# LunettaAV_WIP.net
KiCad netlist of a schematic drawn in EAGLE
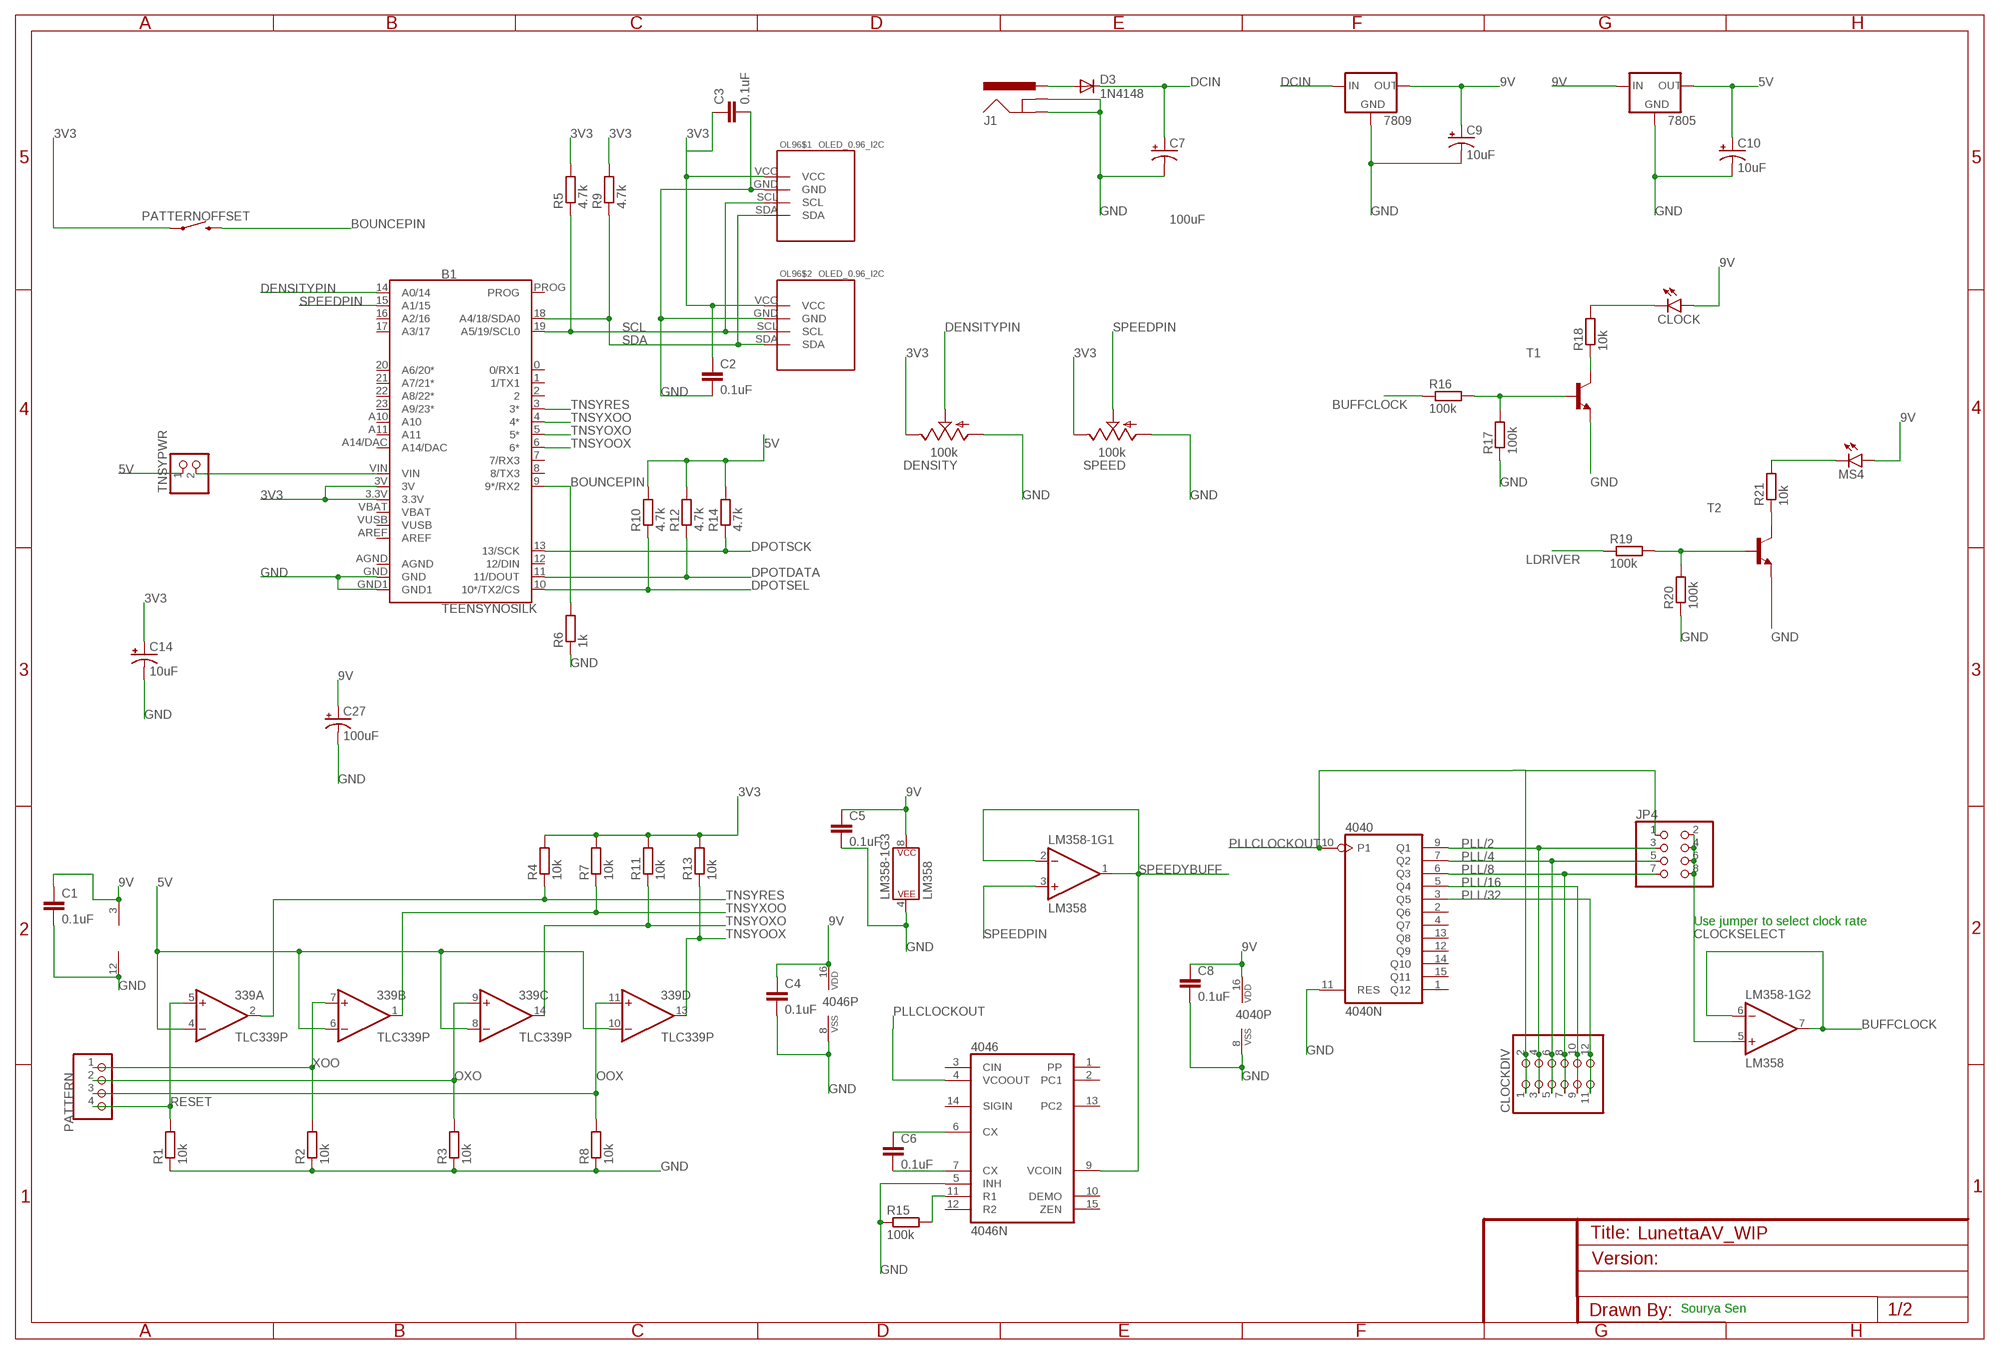
[diagram p0: schematic, sheet 1]
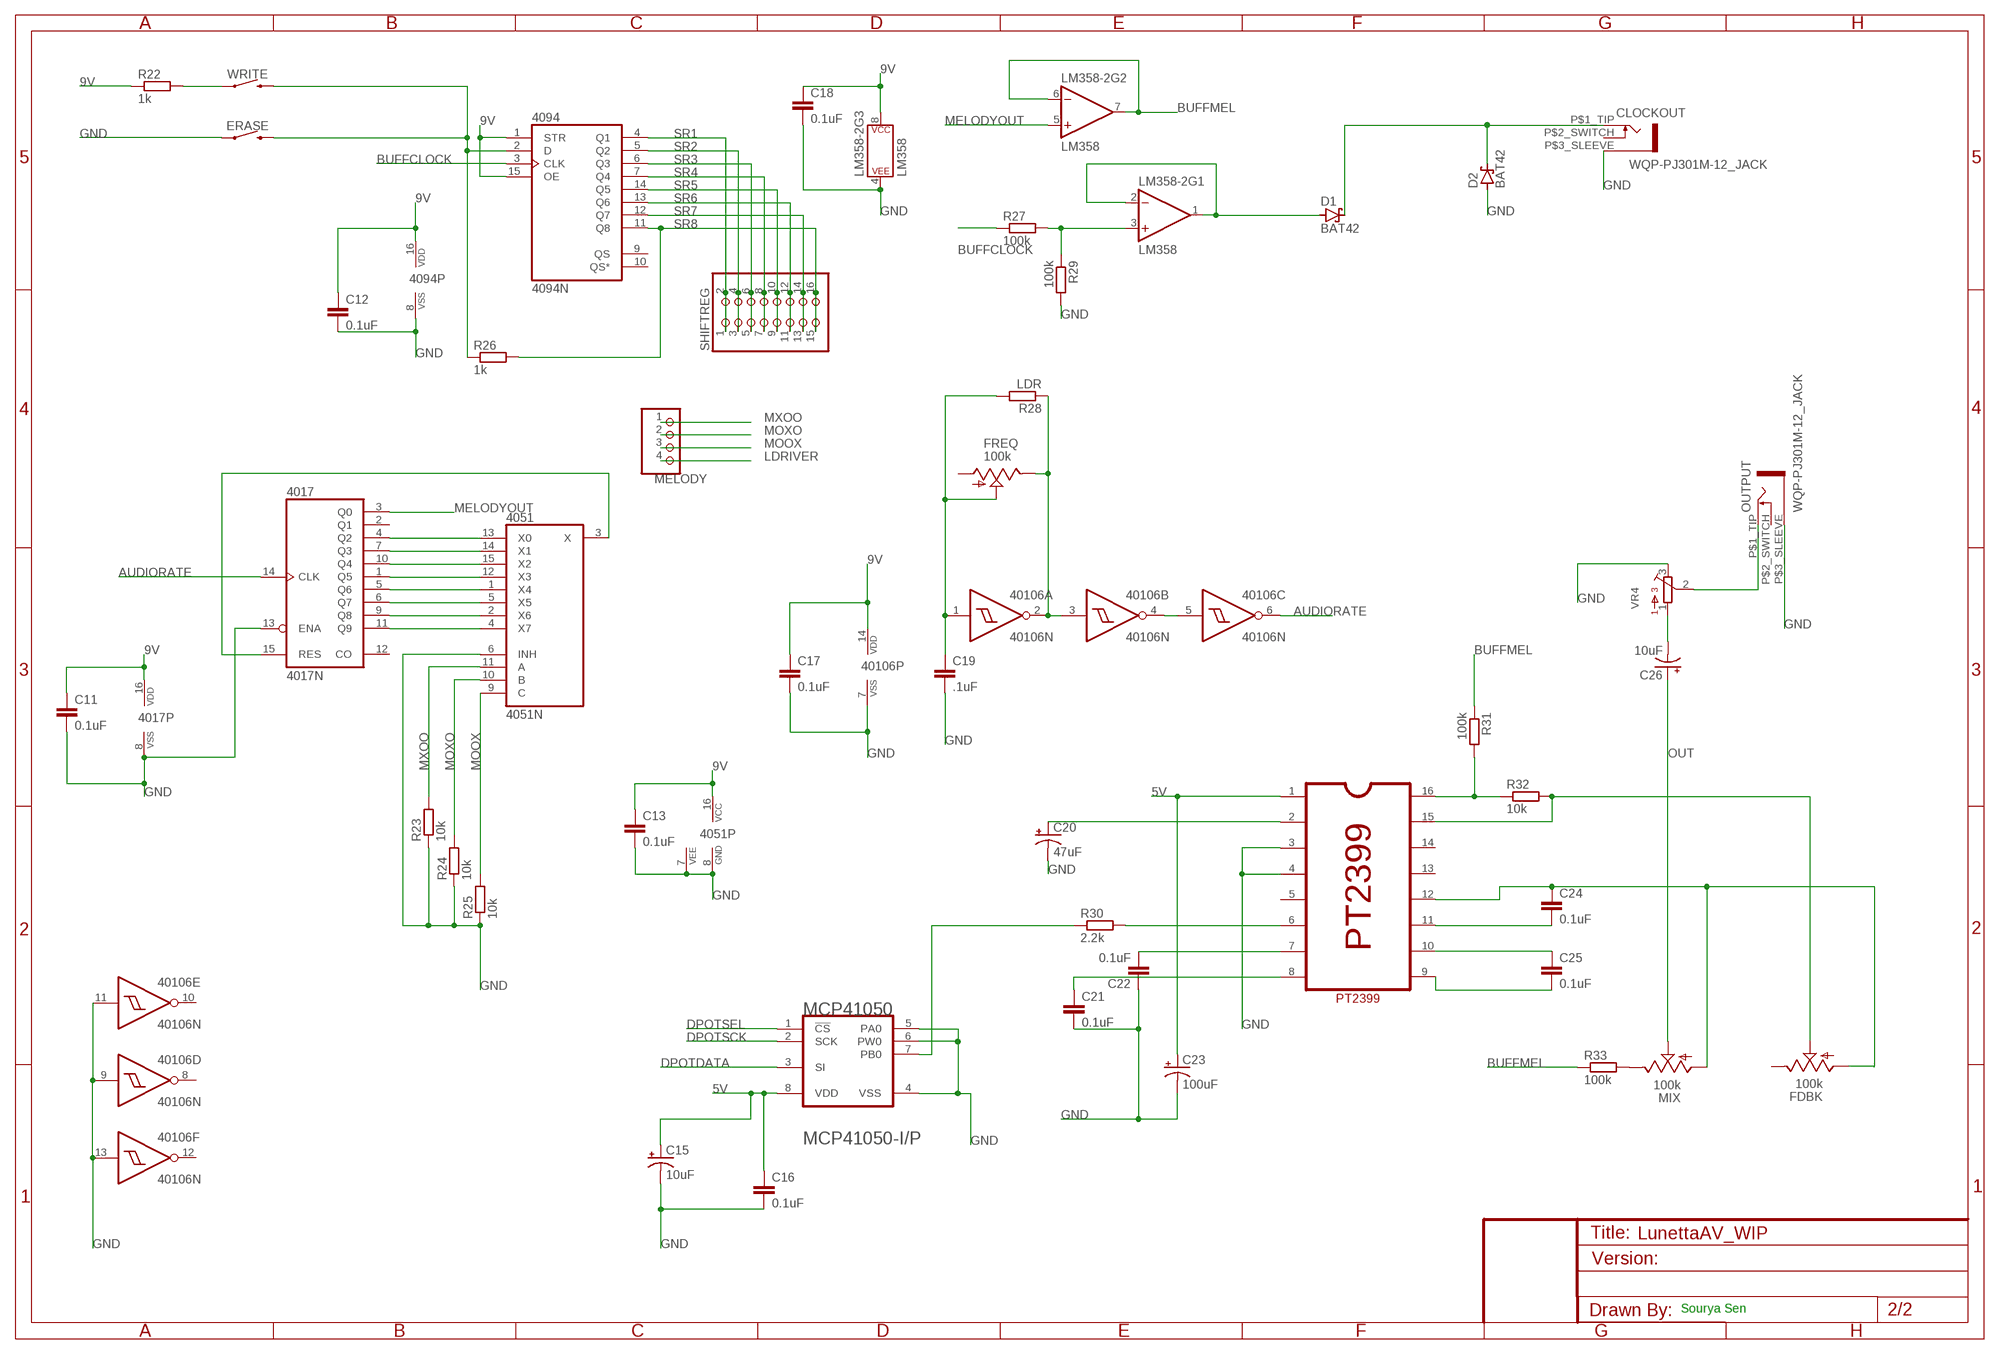
[diagram p1: schematic, sheet 2]

(export (version "E")
  (design (tool "Eeschema 10.0.6"))
  (components
    (comp (ref "4017")
      (value "4017N")
      (footprint "eagle-import:DIL16")
      (libsource (lib "eagle-import") (part "4017N"))
    )
    (comp (ref "4051")
      (value "4051N")
      (footprint "eagle-import:DIL16")
      (libsource (lib "eagle-import") (part "4051N"))
    )
    (comp (ref "4094")
      (value "4094N")
      (footprint "eagle-import:DIL16")
      (libsource (lib "eagle-import") (part "4094N"))
    )
    (comp (ref "40106")
      (value "40106N")
      (footprint "eagle-import:DIL14")
      (libsource (lib "eagle-import") (part "40106N"))
    )
    (comp (ref "C11")
      (value "0.1uF")
      (footprint "eagle-import:CAP-PTH-SMALL-KIT")
      (libsource (lib "eagle-import") (part "0.1UF-KIT-EZ-50V-20%"))
    )
    (comp (ref "C12")
      (value "0.1uF")
      (footprint "eagle-import:CAP-PTH-SMALL-KIT")
      (libsource (lib "eagle-import") (part "0.1UF-KIT-EZ-50V-20%"))
    )
    (comp (ref "C13")
      (value "0.1uF")
      (footprint "eagle-import:CAP-PTH-SMALL-KIT")
      (libsource (lib "eagle-import") (part "0.1UF-KIT-EZ-50V-20%"))
    )
    (comp (ref "C15")
      (value "10uF")
      (footprint "eagle-import:CPOL-RADIAL-2.5MM-5MM")
      (libsource (lib "eagle-import") (part "10UF-POLAR-RADIAL-2.5MM-25V-20%"))
    )
    (comp (ref "C16")
      (value "0.1uF")
      (footprint "eagle-import:CAP-PTH-SMALL-KIT")
      (libsource (lib "eagle-import") (part "0.1UF-KIT-EZ-50V-20%"))
    )
    (comp (ref "C17")
      (value "0.1uF")
      (footprint "eagle-import:CAP-PTH-SMALL-KIT")
      (libsource (lib "eagle-import") (part "0.1UF-KIT-EZ-50V-20%"))
    )
    (comp (ref "C18")
      (value "0.1uF")
      (footprint "eagle-import:CAP-PTH-SMALL-KIT")
      (libsource (lib "eagle-import") (part "0.1UF-KIT-EZ-50V-20%"))
    )
    (comp (ref "C19")
      (value ".1uF")
      (footprint "eagle-import:C5B3.5")
      (libsource (lib "eagle-import") (part "C5/3.5"))
    )
    (comp (ref "C20")
      (value "47uF")
      (footprint "eagle-import:CPOL-RADIAL-2.5MM-5MM")
      (libsource (lib "eagle-import") (part "10UF-POLAR-RADIAL-2.5MM-25V-20%"))
    )
    (comp (ref "C21")
      (value "0.1uF")
      (footprint "eagle-import:CAP-PTH-SMALL-KIT")
      (libsource (lib "eagle-import") (part "0.1UF-KIT-EZ-50V-20%"))
    )
    (comp (ref "C22")
      (value "0.1uF")
      (footprint "eagle-import:CAP-PTH-SMALL-KIT")
      (libsource (lib "eagle-import") (part "0.1UF-KIT-EZ-50V-20%"))
    )
    (comp (ref "C23")
      (value "100uF")
      (footprint "eagle-import:CPOL-RADIAL-2.5MM-6.5MM")
      (libsource (lib "eagle-import") (part "100UF-POLAR-RADIAL-2.5MM-25V-20%"))
    )
    (comp (ref "C24")
      (value "0.1uF")
      (footprint "eagle-import:CAP-PTH-SMALL-KIT")
      (libsource (lib "eagle-import") (part "0.1UF-KIT-EZ-50V-20%"))
    )
    (comp (ref "C25")
      (value "0.1uF")
      (footprint "eagle-import:CAP-PTH-SMALL-KIT")
      (libsource (lib "eagle-import") (part "0.1UF-KIT-EZ-50V-20%"))
    )
    (comp (ref "C26")
      (value "10uF")
      (footprint "eagle-import:CPOL-RADIAL-2.5MM-5MM")
      (libsource (lib "eagle-import") (part "10UF-POLAR-RADIAL-2.5MM-25V-20%"))
    )
    (comp (ref "CLOCKOUT")
      (value "WQP-PJ301M-12_JACK")
      (footprint "eagle-import:WQP-PJ301M-12_JACK")
      (libsource (lib "eagle-import") (part "WQP-PJ301M-12_JACK"))
    )
    (comp (ref "D1")
      (value "BAT42")
      (footprint "eagle-import:DO35-10")
      (libsource (lib "eagle-import") (part "BAT42"))
    )
    (comp (ref "D2")
      (value "BAT42")
      (footprint "eagle-import:DO35-10")
      (libsource (lib "eagle-import") (part "BAT42"))
    )
    (comp (ref "ERASE")
      (value "MOMENTARY-SWITCH-SPST-PTH-12MM")
      (footprint "eagle-import:TACTILE_SWITCH_PTH_12MM")
      (libsource (lib "eagle-import") (part "MOMENTARY-SWITCH-SPST-PTH-12MM"))
    )
    (comp (ref "FDBK")
      (value "100k")
      (footprint "eagle-import:9MM_SNAP-IN_POT")
      (libsource (lib "eagle-import") (part "9MM_SNAP-IN_POT_"))
    )
    (comp (ref "FREQ")
      (value "100k")
      (footprint "eagle-import:9MM_SNAP-IN_POT")
      (libsource (lib "eagle-import") (part "9MM_SNAP-IN_POT_"))
    )
    (comp (ref "LM358-2")
      (value "LM358")
      (footprint "eagle-import:DIP08")
      (libsource (lib "eagle-import") (part "LM358"))
    )
    (comp (ref "MCP41050")
      (value "MCP41050")
      (footprint "eagle-import:MICROCHIP_MCP41050-I-P_0")
      (fields (field (name "MF") "Microchip") (field (name "MPN") "MCP41050-I/P"))
      (libsource (lib "eagle-import") (part "MICROCHIP_MCP41050-I-PMICROCHIP_MCP41050-I-P_0_0"))
    )
    (comp (ref "MELODY")
      (value "PINHD-1X4")
      (footprint "eagle-import:1X04")
      (libsource (lib "eagle-import") (part "PINHD-1X4"))
    )
    (comp (ref "MIX")
      (value "100k")
      (footprint "eagle-import:9MM_SNAP-IN_POT")
      (libsource (lib "eagle-import") (part "9MM_SNAP-IN_POT_"))
    )
    (comp (ref "OUTPUT")
      (value "WQP-PJ301M-12_JACK")
      (footprint "eagle-import:WQP-PJ301M-12_JACK")
      (libsource (lib "eagle-import") (part "WQP-PJ301M-12_JACK"))
    )
    (comp (ref "PT2399")
      (value "PT2399")
      (footprint "eagle-import:DIP-16")
      (libsource (lib "eagle-import") (part "PT2399"))
    )
    (comp (ref "R22")
      (value "1k")
      (footprint "eagle-import:7MM_RESISTOR")
      (libsource (lib "eagle-import") (part "RESISTOR7MM"))
    )
    (comp (ref "R23")
      (value "10k")
      (footprint "eagle-import:7MM_RESISTOR")
      (libsource (lib "eagle-import") (part "RESISTOR7MM"))
    )
    (comp (ref "R24")
      (value "10k")
      (footprint "eagle-import:7MM_RESISTOR")
      (libsource (lib "eagle-import") (part "RESISTOR7MM"))
    )
    (comp (ref "R25")
      (value "10k")
      (footprint "eagle-import:7MM_RESISTOR")
      (libsource (lib "eagle-import") (part "RESISTOR7MM"))
    )
    (comp (ref "R26")
      (value "1k")
      (footprint "eagle-import:7MM_RESISTOR")
      (libsource (lib "eagle-import") (part "RESISTOR7MM"))
    )
    (comp (ref "R27")
      (value "100k")
      (footprint "eagle-import:7MM_RESISTOR")
      (libsource (lib "eagle-import") (part "RESISTOR7MM"))
    )
    (comp (ref "R28")
      (value "LDR")
      (footprint "eagle-import:0204V")
      (libsource (lib "eagle-import") (part "R-EU_0204/2V"))
    )
    (comp (ref "R29")
      (value "100k")
      (footprint "eagle-import:7MM_RESISTOR")
      (libsource (lib "eagle-import") (part "RESISTOR7MM"))
    )
    (comp (ref "R30")
      (value "2.2k")
      (footprint "eagle-import:7MM_RESISTOR")
      (libsource (lib "eagle-import") (part "RESISTOR7MM"))
    )
    (comp (ref "R31")
      (value "100k")
      (footprint "eagle-import:7MM_RESISTOR")
      (libsource (lib "eagle-import") (part "RESISTOR7MM"))
    )
    (comp (ref "R32")
      (value "10k")
      (footprint "eagle-import:7MM_RESISTOR")
      (libsource (lib "eagle-import") (part "RESISTOR7MM"))
    )
    (comp (ref "R33")
      (value "100k")
      (footprint "eagle-import:7MM_RESISTOR")
      (libsource (lib "eagle-import") (part "RESISTOR7MM"))
    )
    (comp (ref "SHIFTREG")
      (value "PINHD-2X8")
      (footprint "eagle-import:2X08")
      (libsource (lib "eagle-import") (part "PINHD-2X8"))
    )
    (comp (ref "VR4")
      (value "BOURNS_3362P_TRIMMERP")
      (footprint "eagle-import:BOURNS_3362P_TRIMMER")
      (libsource (lib "eagle-import") (part "BOURNS_3362P_TRIMMERP"))
    )
    (comp (ref "WRITE")
      (value "MOMENTARY-SWITCH-SPST-PTH-12MM")
      (footprint "eagle-import:TACTILE_SWITCH_PTH_12MM")
      (libsource (lib "eagle-import") (part "MOMENTARY-SWITCH-SPST-PTH-12MM"))
    )
    (comp (ref "339")
      (value "TLC339P")
      (footprint "eagle-import:DIL14")
      (libsource (lib "eagle-import") (part "TLC339P"))
    )
    (comp (ref "4040")
      (value "4040N")
      (footprint "eagle-import:DIL16")
      (libsource (lib "eagle-import") (part "4040N"))
    )
    (comp (ref "4046")
      (value "4046N")
      (footprint "eagle-import:DIL16")
      (libsource (lib "eagle-import") (part "4046N"))
    )
    (comp (ref "7805")
      (value "7805")
      (footprint "eagle-import:78XXS")
      (libsource (lib "eagle-import") (part "78XXS"))
    )
    (comp (ref "7809")
      (value "7809")
      (footprint "eagle-import:78XXS")
      (libsource (lib "eagle-import") (part "78XXS"))
    )
    (comp (ref "B1")
      (value "TEENSYNOSILK")
      (footprint "eagle-import:TEENSY_NOSILK")
      (libsource (lib "eagle-import") (part "TEENSYNOSILK"))
    )
    (comp (ref "C1")
      (value "0.1uF")
      (footprint "eagle-import:CAP-PTH-SMALL-KIT")
      (libsource (lib "eagle-import") (part "0.1UF-KIT-EZ-50V-20%"))
    )
    (comp (ref "C2")
      (value "0.1uF")
      (footprint "eagle-import:CAP-PTH-SMALL-KIT")
      (libsource (lib "eagle-import") (part "0.1UF-KIT-EZ-50V-20%"))
    )
    (comp (ref "C3")
      (value "0.1uF")
      (footprint "eagle-import:CAP-PTH-SMALL-KIT")
      (libsource (lib "eagle-import") (part "0.1UF-KIT-EZ-50V-20%"))
    )
    (comp (ref "C4")
      (value "0.1uF")
      (footprint "eagle-import:CAP-PTH-SMALL-KIT")
      (libsource (lib "eagle-import") (part "0.1UF-KIT-EZ-50V-20%"))
    )
    (comp (ref "C5")
      (value "0.1uF")
      (footprint "eagle-import:CAP-PTH-SMALL-KIT")
      (libsource (lib "eagle-import") (part "0.1UF-KIT-EZ-50V-20%"))
    )
    (comp (ref "C6")
      (value "0.1uF")
      (footprint "eagle-import:CAP-PTH-SMALL-KIT")
      (libsource (lib "eagle-import") (part "0.1UF-KIT-EZ-50V-20%"))
    )
    (comp (ref "C7")
      (value "100uF")
      (footprint "eagle-import:CPOL-RADIAL-2.5MM-6.5MM")
      (libsource (lib "eagle-import") (part "100UF-POLAR-RADIAL-2.5MM-25V-20%"))
    )
    (comp (ref "C8")
      (value "0.1uF")
      (footprint "eagle-import:CAP-PTH-SMALL-KIT")
      (libsource (lib "eagle-import") (part "0.1UF-KIT-EZ-50V-20%"))
    )
    (comp (ref "C9")
      (value "10uF")
      (footprint "eagle-import:CPOL-RADIAL-2.5MM-5MM")
      (libsource (lib "eagle-import") (part "10UF-POLAR-RADIAL-2.5MM-25V-20%"))
    )
    (comp (ref "C10")
      (value "10uF")
      (footprint "eagle-import:CPOL-RADIAL-2.5MM-5MM")
      (libsource (lib "eagle-import") (part "10UF-POLAR-RADIAL-2.5MM-25V-20%"))
    )
    (comp (ref "C14")
      (value "10uF")
      (footprint "eagle-import:CPOL-RADIAL-2.5MM-5MM")
      (libsource (lib "eagle-import") (part "10UF-POLAR-RADIAL-2.5MM-25V-20%"))
    )
    (comp (ref "C27")
      (value "100uF")
      (footprint "eagle-import:CPOL-RADIAL-2.5MM-6.5MM")
      (libsource (lib "eagle-import") (part "100UF-POLAR-RADIAL-2.5MM-25V-20%"))
    )
    (comp (ref "CLOCK")
      (value "LED3MM")
      (footprint "eagle-import:LED_3MM")
      (libsource (lib "eagle-import") (part "LED3MM"))
    )
    (comp (ref "CLOCKDIV")
      (value "PINHD-2X6")
      (footprint "eagle-import:2X06")
      (libsource (lib "eagle-import") (part "PINHD-2X6"))
    )
    (comp (ref "D3")
      (value "1N4148")
      (footprint "eagle-import:DO35-7")
      (libsource (lib "eagle-import") (part "SMALL_DIODEDO35-7"))
    )
    (comp (ref "DENSITY")
      (value "100k")
      (footprint "eagle-import:9MM_SNAP-IN_POT")
      (libsource (lib "eagle-import") (part "9MM_SNAP-IN_POT_"))
    )
    (comp (ref "J1")
      (value "POWER_JACKPOWER_JACK_SLOT")
      (footprint "eagle-import:POWER_JACK_PTH_SLOT")
      (libsource (lib "eagle-import") (part "POWER_JACKPOWER_JACK_SLOT"))
    )
    (comp (ref "JP4")
      (value "PINHD-2X4")
      (footprint "eagle-import:2X04")
      (libsource (lib "eagle-import") (part "PINHD-2X4"))
    )
    (comp (ref "LM358-1")
      (value "LM358")
      (footprint "eagle-import:DIP08")
      (libsource (lib "eagle-import") (part "LM358"))
    )
    (comp (ref "MS4")
      (value "LED3MM")
      (footprint "eagle-import:LED_3MM")
      (libsource (lib "eagle-import") (part "LED3MM"))
    )
    (comp (ref "OL96$1")
      (value "OLED_0.96_I2C")
      (footprint "eagle-import:OLED_0.96_I2C")
      (libsource (lib "eagle-import") (part "OLED_0.96_I2C"))
    )
    (comp (ref "OL96$2")
      (value "OLED_0.96_I2C")
      (footprint "eagle-import:OLED_0.96_I2C")
      (libsource (lib "eagle-import") (part "OLED_0.96_I2C"))
    )
    (comp (ref "PATTERN")
      (value "PINHD-1X4")
      (footprint "eagle-import:1X04")
      (libsource (lib "eagle-import") (part "PINHD-1X4"))
    )
    (comp (ref "PATTERNOFFSET")
      (value "MOMENTARY-SWITCH-SPST-PTH-12MM")
      (footprint "eagle-import:TACTILE_SWITCH_PTH_12MM")
      (libsource (lib "eagle-import") (part "MOMENTARY-SWITCH-SPST-PTH-12MM"))
    )
    (comp (ref "R1")
      (value "10k")
      (footprint "eagle-import:7MM_RESISTOR")
      (libsource (lib "eagle-import") (part "RESISTOR7MM"))
    )
    (comp (ref "R2")
      (value "10k")
      (footprint "eagle-import:7MM_RESISTOR")
      (libsource (lib "eagle-import") (part "RESISTOR7MM"))
    )
    (comp (ref "R3")
      (value "10k")
      (footprint "eagle-import:7MM_RESISTOR")
      (libsource (lib "eagle-import") (part "RESISTOR7MM"))
    )
    (comp (ref "R4")
      (value "10k")
      (footprint "eagle-import:7MM_RESISTOR")
      (libsource (lib "eagle-import") (part "RESISTOR7MM"))
    )
    (comp (ref "R5")
      (value "4.7k")
      (footprint "eagle-import:7MM_RESISTOR")
      (libsource (lib "eagle-import") (part "RESISTOR7MM"))
    )
    (comp (ref "R6")
      (value "1k")
      (footprint "eagle-import:7MM_RESISTOR")
      (libsource (lib "eagle-import") (part "RESISTOR7MM"))
    )
    (comp (ref "R7")
      (value "10k")
      (footprint "eagle-import:7MM_RESISTOR")
      (libsource (lib "eagle-import") (part "RESISTOR7MM"))
    )
    (comp (ref "R8")
      (value "10k")
      (footprint "eagle-import:7MM_RESISTOR")
      (libsource (lib "eagle-import") (part "RESISTOR7MM"))
    )
    (comp (ref "R9")
      (value "4.7k")
      (footprint "eagle-import:7MM_RESISTOR")
      (libsource (lib "eagle-import") (part "RESISTOR7MM"))
    )
    (comp (ref "R10")
      (value "4.7k")
      (footprint "eagle-import:7MM_RESISTOR")
      (libsource (lib "eagle-import") (part "RESISTOR7MM"))
    )
    (comp (ref "R11")
      (value "10k")
      (footprint "eagle-import:7MM_RESISTOR")
      (libsource (lib "eagle-import") (part "RESISTOR7MM"))
    )
    (comp (ref "R12")
      (value "4.7k")
      (footprint "eagle-import:7MM_RESISTOR")
      (libsource (lib "eagle-import") (part "RESISTOR7MM"))
    )
    (comp (ref "R13")
      (value "10k")
      (footprint "eagle-import:7MM_RESISTOR")
      (libsource (lib "eagle-import") (part "RESISTOR7MM"))
    )
    (comp (ref "R14")
      (value "4.7k")
      (footprint "eagle-import:7MM_RESISTOR")
      (libsource (lib "eagle-import") (part "RESISTOR7MM"))
    )
    (comp (ref "R15")
      (value "100k")
      (footprint "eagle-import:7MM_RESISTOR")
      (libsource (lib "eagle-import") (part "RESISTOR7MM"))
    )
    (comp (ref "R16")
      (value "100k")
      (footprint "eagle-import:7MM_RESISTOR")
      (libsource (lib "eagle-import") (part "RESISTOR7MM"))
    )
    (comp (ref "R17")
      (value "100k")
      (footprint "eagle-import:7MM_RESISTOR")
      (libsource (lib "eagle-import") (part "RESISTOR7MM"))
    )
    (comp (ref "R18")
      (value "10k")
      (footprint "eagle-import:7MM_RESISTOR")
      (libsource (lib "eagle-import") (part "RESISTOR7MM"))
    )
    (comp (ref "R19")
      (value "100k")
      (footprint "eagle-import:7MM_RESISTOR")
      (libsource (lib "eagle-import") (part "RESISTOR7MM"))
    )
    (comp (ref "R20")
      (value "100k")
      (footprint "eagle-import:7MM_RESISTOR")
      (libsource (lib "eagle-import") (part "RESISTOR7MM"))
    )
    (comp (ref "R21")
      (value "10k")
      (footprint "eagle-import:7MM_RESISTOR")
      (libsource (lib "eagle-import") (part "RESISTOR7MM"))
    )
    (comp (ref "SPEED")
      (value "100k")
      (footprint "eagle-import:9MM_SNAP-IN_POT")
      (libsource (lib "eagle-import") (part "9MM_SNAP-IN_POT_"))
    )
    (comp (ref "T1")
      (value "2N4401-NPN-TO92-EBC")
      (footprint "eagle-import:TO92-EBC")
      (libsource (lib "eagle-import") (part "-NPN-TO92-EBC2N4401"))
    )
    (comp (ref "T2")
      (value "2N4401-NPN-TO92-EBC")
      (footprint "eagle-import:TO92-EBC")
      (libsource (lib "eagle-import") (part "-NPN-TO92-EBC2N4401"))
    )
    (comp (ref "TNSYPWR")
      (value "PINHD-1X2")
      (footprint "eagle-import:1X02")
      (libsource (lib "eagle-import") (part "PINHD-1X2"))
    )
  )
  (nets
    (net (code "1") (name "3V3") (class "Default")
      (node (ref "B1") (pin "3.3V") (pinfunction "3.3V_3.3V") (pintype "power_in"))
      (node (ref "B1") (pin "3V") (pinfunction "3V_3V") (pintype "power_in"))
      (node (ref "C14") (pin "1") (pinfunction "+_1") (pintype "passive"))
      (node (ref "C2") (pin "1") (pinfunction "1_1") (pintype "passive"))
      (node (ref "C3") (pin "1") (pinfunction "1_1") (pintype "passive"))
      (node (ref "DENSITY") (pin "3") (pinfunction "E_3") (pintype "passive"))
      (node (ref "OL96$1") (pin "VCC") (pinfunction "VCC_VCC") (pintype "bidirectional"))
      (node (ref "OL96$2") (pin "VCC") (pinfunction "VCC_VCC") (pintype "bidirectional"))
      (node (ref "PATTERNOFFSET") (pin "1") (pinfunction "1_1") (pintype "passive"))
      (node (ref "R11") (pin "2") (pinfunction "2_2") (pintype "passive"))
      (node (ref "R13") (pin "2") (pinfunction "2_2") (pintype "passive"))
      (node (ref "R4") (pin "2") (pinfunction "2_2") (pintype "passive"))
      (node (ref "R5") (pin "2") (pinfunction "2_2") (pintype "passive"))
      (node (ref "R7") (pin "2") (pinfunction "2_2") (pintype "passive"))
      (node (ref "R9") (pin "2") (pinfunction "2_2") (pintype "passive"))
      (node (ref "SPEED") (pin "3") (pinfunction "E_3") (pintype "passive"))
    )
    (net (code "2") (name "5V") (class "Default")
      (node (ref "339") (pin "10") (pinfunction "-IN_10") (pintype "input"))
      (node (ref "339") (pin "4") (pinfunction "-IN_4") (pintype "input"))
      (node (ref "339") (pin "6") (pinfunction "-IN_6") (pintype "input"))
      (node (ref "339") (pin "8") (pinfunction "-IN_8") (pintype "input"))
      (node (ref "7805") (pin "OUT") (pinfunction "OUT_OUT") (pintype "passive"))
      (node (ref "C10") (pin "1") (pinfunction "+_1") (pintype "passive"))
      (node (ref "C15") (pin "1") (pinfunction "+_1") (pintype "passive"))
      (node (ref "C16") (pin "1") (pinfunction "1_1") (pintype "passive"))
      (node (ref "C23") (pin "1") (pinfunction "+_1") (pintype "passive"))
      (node (ref "MCP41050") (pin "8") (pinfunction "VDD_8") (pintype "power_in"))
      (node (ref "PT2399") (pin "1") (pinfunction "1_1") (pintype "bidirectional"))
      (node (ref "R10") (pin "2") (pinfunction "2_2") (pintype "passive"))
      (node (ref "R12") (pin "2") (pinfunction "2_2") (pintype "passive"))
      (node (ref "R14") (pin "2") (pinfunction "2_2") (pintype "passive"))
      (node (ref "TNSYPWR") (pin "1") (pinfunction "1_1") (pintype "passive"))
    )
    (net (code "3") (name "9V") (class "Default")
      (node (ref "339") (pin "3") (pinfunction "V+_3") (pintype "power_in"))
      (node (ref "40106") (pin "14") (pinfunction "VDD_14") (pintype "power_in"))
      (node (ref "4017") (pin "16") (pinfunction "VDD_16") (pintype "power_in"))
      (node (ref "4040") (pin "16") (pinfunction "VDD_16") (pintype "power_in"))
      (node (ref "4046") (pin "16") (pinfunction "VDD_16") (pintype "power_in"))
      (node (ref "4051") (pin "16") (pinfunction "VCC_16") (pintype "power_in"))
      (node (ref "4094") (pin "1") (pinfunction "STR_1") (pintype "input"))
      (node (ref "4094") (pin "15") (pinfunction "OE_15") (pintype "input"))
      (node (ref "4094") (pin "16") (pinfunction "VDD_16") (pintype "power_in"))
      (node (ref "7805") (pin "IN") (pinfunction "IN_IN") (pintype "input"))
      (node (ref "7809") (pin "OUT") (pinfunction "OUT_OUT") (pintype "passive"))
      (node (ref "C1") (pin "1") (pinfunction "1_1") (pintype "passive"))
      (node (ref "C11") (pin "1") (pinfunction "1_1") (pintype "passive"))
      (node (ref "C12") (pin "1") (pinfunction "1_1") (pintype "passive"))
      (node (ref "C13") (pin "1") (pinfunction "1_1") (pintype "passive"))
      (node (ref "C17") (pin "1") (pinfunction "1_1") (pintype "passive"))
      (node (ref "C18") (pin "1") (pinfunction "1_1") (pintype "passive"))
      (node (ref "C27") (pin "1") (pinfunction "+_1") (pintype "passive"))
      (node (ref "C4") (pin "1") (pinfunction "1_1") (pintype "passive"))
      (node (ref "C5") (pin "1") (pinfunction "1_1") (pintype "passive"))
      (node (ref "C8") (pin "1") (pinfunction "1_1") (pintype "passive"))
      (node (ref "C9") (pin "1") (pinfunction "+_1") (pintype "passive"))
      (node (ref "CLOCK") (pin "A") (pinfunction "A_A") (pintype "passive"))
      (node (ref "LM358-1") (pin "8") (pinfunction "P$V+_8") (pintype "bidirectional"))
      (node (ref "LM358-2") (pin "8") (pinfunction "P$V+_8") (pintype "bidirectional"))
      (node (ref "MS4") (pin "A") (pinfunction "A_A") (pintype "passive"))
      (node (ref "R22") (pin "1") (pinfunction "1_1") (pintype "passive"))
    )
    (net (code "4") (name "AGND") (class "Default")
      (node (ref "B1") (pin "AGND") (pinfunction "AGND_AGND") (pintype "power_in"))
    )
    (net (code "5") (name "AUDIORATE") (class "Default")
      (node (ref "40106") (pin "6") (pinfunction "O_6") (pintype "output"))
      (node (ref "4017") (pin "14") (pinfunction "CLK_14") (pintype "input"))
    )
    (net (code "6") (name "BOUNCEPIN") (class "Default")
      (node (ref "B1") (pin "9") (pinfunction "9*/RX2_9") (pintype "bidirectional"))
      (node (ref "PATTERNOFFSET") (pin "3") (pinfunction "2_3") (pintype "passive"))
      (node (ref "R6") (pin "2") (pinfunction "2_2") (pintype "passive"))
    )
    (net (code "7") (name "BUFFCLOCK") (class "Default")
      (node (ref "4094") (pin "3") (pinfunction "CLK_3") (pintype "input"))
      (node (ref "LM358-1") (pin "6") (pinfunction "-IN_6") (pintype "input"))
      (node (ref "LM358-1") (pin "7") (pinfunction "OUT_7") (pintype "output"))
      (node (ref "R16") (pin "1") (pinfunction "1_1") (pintype "passive"))
      (node (ref "R27") (pin "1") (pinfunction "1_1") (pintype "passive"))
    )
    (net (code "8") (name "BUFFMEL") (class "Default")
      (node (ref "LM358-2") (pin "6") (pinfunction "-IN_6") (pintype "input"))
      (node (ref "LM358-2") (pin "7") (pinfunction "OUT_7") (pintype "output"))
      (node (ref "R31") (pin "1") (pinfunction "1_1") (pintype "passive"))
      (node (ref "R33") (pin "1") (pinfunction "1_1") (pintype "passive"))
    )
    (net (code "9") (name "CLOCKSELECT") (class "Default")
      (node (ref "JP4") (pin "2") (pinfunction "2_2") (pintype "passive"))
      (node (ref "JP4") (pin "4") (pinfunction "4_4") (pintype "passive"))
      (node (ref "JP4") (pin "6") (pinfunction "6_6") (pintype "passive"))
      (node (ref "JP4") (pin "8") (pinfunction "8_8") (pintype "passive"))
      (node (ref "LM358-1") (pin "5") (pinfunction "+IN_5") (pintype "input"))
    )
    (net (code "10") (name "DCIN") (class "Default")
      (node (ref "7809") (pin "IN") (pinfunction "IN_IN") (pintype "input"))
      (node (ref "C7") (pin "1") (pinfunction "+_1") (pintype "passive"))
      (node (ref "D3") (pin "C") (pinfunction "C_C") (pintype "passive"))
    )
    (net (code "11") (name "DENSITYPIN") (class "Default")
      (node (ref "B1") (pin "14") (pinfunction "A0/14_14") (pintype "bidirectional"))
      (node (ref "DENSITY") (pin "2") (pinfunction "S_2") (pintype "passive"))
    )
    (net (code "12") (name "DPOTDATA") (class "Default")
      (node (ref "B1") (pin "11") (pinfunction "11/DOUT_11") (pintype "bidirectional"))
      (node (ref "MCP41050") (pin "3") (pinfunction "SI_3") (pintype "input"))
      (node (ref "R12") (pin "1") (pinfunction "1_1") (pintype "passive"))
    )
    (net (code "13") (name "DPOTSCK") (class "Default")
      (node (ref "B1") (pin "13") (pinfunction "13/SCK_13") (pintype "bidirectional"))
      (node (ref "MCP41050") (pin "2") (pinfunction "SCK_2") (pintype "input"))
      (node (ref "R14") (pin "1") (pinfunction "1_1") (pintype "passive"))
    )
    (net (code "14") (name "DPOTSEL") (class "Default")
      (node (ref "B1") (pin "10") (pinfunction "10*/TX2/CS_10") (pintype "bidirectional"))
      (node (ref "MCP41050") (pin "1") (pinfunction "~{CS}_1") (pintype "input"))
      (node (ref "R10") (pin "1") (pinfunction "1_1") (pintype "passive"))
    )
    (net (code "15") (name "GND") (class "Default")
      (node (ref "339") (pin "12") (pinfunction "V-_12") (pintype "power_in"))
      (node (ref "40106") (pin "11") (pinfunction "I_11") (pintype "input"))
      (node (ref "40106") (pin "13") (pinfunction "I_13") (pintype "input"))
      (node (ref "40106") (pin "7") (pinfunction "VSS_7") (pintype "power_in"))
      (node (ref "40106") (pin "9") (pinfunction "I_9") (pintype "input"))
      (node (ref "4017") (pin "13") (pinfunction "ENA_13") (pintype "input"))
      (node (ref "4017") (pin "8") (pinfunction "VSS_8") (pintype "power_in"))
      (node (ref "4040") (pin "11") (pinfunction "RES_11") (pintype "input"))
      (node (ref "4040") (pin "8") (pinfunction "VSS_8") (pintype "power_in"))
      (node (ref "4046") (pin "5") (pinfunction "INH_5") (pintype "input"))
      (node (ref "4046") (pin "8") (pinfunction "VSS_8") (pintype "power_in"))
      (node (ref "4051") (pin "6") (pinfunction "INH_6") (pintype "input"))
      (node (ref "4051") (pin "7") (pinfunction "VEE_7") (pintype "power_in"))
      (node (ref "4051") (pin "8") (pinfunction "GND_8") (pintype "power_in"))
      (node (ref "4094") (pin "8") (pinfunction "VSS_8") (pintype "power_in"))
      (node (ref "7805") (pin "GND") (pinfunction "GND_GND") (pintype "input"))
      (node (ref "7809") (pin "GND") (pinfunction "GND_GND") (pintype "input"))
      (node (ref "B1") (pin "GND") (pinfunction "GND_GND") (pintype "power_in"))
      (node (ref "B1") (pin "GND1") (pinfunction "GND1_GND1") (pintype "power_in"))
      (node (ref "C1") (pin "2") (pinfunction "2_2") (pintype "passive"))
      (node (ref "C10") (pin "2") (pinfunction "-_2") (pintype "passive"))
      (node (ref "C11") (pin "2") (pinfunction "2_2") (pintype "passive"))
      (node (ref "C12") (pin "2") (pinfunction "2_2") (pintype "passive"))
      (node (ref "C13") (pin "2") (pinfunction "2_2") (pintype "passive"))
      (node (ref "C14") (pin "2") (pinfunction "-_2") (pintype "passive"))
      (node (ref "C15") (pin "2") (pinfunction "-_2") (pintype "passive"))
      (node (ref "C16") (pin "2") (pinfunction "2_2") (pintype "passive"))
      (node (ref "C17") (pin "2") (pinfunction "2_2") (pintype "passive"))
      (node (ref "C18") (pin "2") (pinfunction "2_2") (pintype "passive"))
      (node (ref "C19") (pin "2") (pinfunction "2_2") (pintype "passive"))
      (node (ref "C2") (pin "2") (pinfunction "2_2") (pintype "passive"))
      (node (ref "C20") (pin "2") (pinfunction "-_2") (pintype "passive"))
      (node (ref "C21") (pin "2") (pinfunction "2_2") (pintype "passive"))
      (node (ref "C22") (pin "1") (pinfunction "1_1") (pintype "passive"))
      (node (ref "C23") (pin "2") (pinfunction "-_2") (pintype "passive"))
      (node (ref "C27") (pin "2") (pinfunction "-_2") (pintype "passive"))
      (node (ref "C3") (pin "2") (pinfunction "2_2") (pintype "passive"))
      (node (ref "C4") (pin "2") (pinfunction "2_2") (pintype "passive"))
      (node (ref "C5") (pin "2") (pinfunction "2_2") (pintype "passive"))
      (node (ref "C7") (pin "2") (pinfunction "-_2") (pintype "passive"))
      (node (ref "C8") (pin "2") (pinfunction "2_2") (pintype "passive"))
      (node (ref "C9") (pin "2") (pinfunction "-_2") (pintype "passive"))
      (node (ref "CLOCKOUT") (pin "P$3_SLEEVE") (pinfunction "1_P$3_SLEEVE") (pintype "passive"))
      (node (ref "D2") (pin "A") (pinfunction "A_A") (pintype "passive"))
      (node (ref "DENSITY") (pin "1") (pinfunction "A_1") (pintype "passive"))
      (node (ref "ERASE") (pin "1") (pinfunction "1_1") (pintype "passive"))
      (node (ref "J1") (pin "GND") (pinfunction "GND_GND") (pintype "bidirectional"))
      (node (ref "J1") (pin "GNDBREAK") (pinfunction "GNDBREAK_GNDBREAK") (pintype "bidirectional"))
      (node (ref "LM358-1") (pin "4") (pinfunction "P$V-_4") (pintype "bidirectional"))
      (node (ref "LM358-2") (pin "4") (pinfunction "P$V-_4") (pintype "bidirectional"))
      (node (ref "MCP41050") (pin "4") (pinfunction "VSS_4") (pintype "power_in"))
      (node (ref "MCP41050") (pin "5") (pinfunction "PA0_5") (pintype "passive"))
      (node (ref "MCP41050") (pin "6") (pinfunction "PW0_6") (pintype "passive"))
      (node (ref "OL96$1") (pin "GND") (pinfunction "GND_GND") (pintype "bidirectional"))
      (node (ref "OL96$2") (pin "GND") (pinfunction "GND_GND") (pintype "bidirectional"))
      (node (ref "OUTPUT") (pin "P$3_SLEEVE") (pinfunction "1_P$3_SLEEVE") (pintype "passive"))
      (node (ref "PT2399") (pin "3") (pinfunction "3_3") (pintype "bidirectional"))
      (node (ref "PT2399") (pin "4") (pinfunction "4_4") (pintype "bidirectional"))
      (node (ref "R1") (pin "1") (pinfunction "1_1") (pintype "passive"))
      (node (ref "R15") (pin "1") (pinfunction "1_1") (pintype "passive"))
      (node (ref "R17") (pin "1") (pinfunction "1_1") (pintype "passive"))
      (node (ref "R2") (pin "1") (pinfunction "1_1") (pintype "passive"))
      (node (ref "R20") (pin "1") (pinfunction "1_1") (pintype "passive"))
      (node (ref "R23") (pin "1") (pinfunction "1_1") (pintype "passive"))
      (node (ref "R24") (pin "1") (pinfunction "1_1") (pintype "passive"))
      (node (ref "R25") (pin "1") (pinfunction "1_1") (pintype "passive"))
      (node (ref "R29") (pin "2") (pinfunction "2_2") (pintype "passive"))
      (node (ref "R3") (pin "1") (pinfunction "1_1") (pintype "passive"))
      (node (ref "R6") (pin "1") (pinfunction "1_1") (pintype "passive"))
      (node (ref "R8") (pin "1") (pinfunction "1_1") (pintype "passive"))
      (node (ref "SPEED") (pin "1") (pinfunction "A_1") (pintype "passive"))
      (node (ref "T1") (pin "E") (pinfunction "E_E") (pintype "passive"))
      (node (ref "T2") (pin "E") (pinfunction "E_E") (pintype "passive"))
      (node (ref "VR4") (pin "3") (pinfunction "3_3") (pintype "passive"))
    )
    (net (code "16") (name "LDRIVER") (class "Default")
      (node (ref "MELODY") (pin "4") (pinfunction "4_4") (pintype "passive"))
      (node (ref "R19") (pin "1") (pinfunction "1_1") (pintype "passive"))
    )
    (net (code "17") (name "MELODYOUT") (class "Default")
      (node (ref "4017") (pin "3") (pinfunction "Q0_3") (pintype "output"))
      (node (ref "LM358-2") (pin "5") (pinfunction "+IN_5") (pintype "input"))
    )
    (net (code "18") (name "MOOX") (class "Default")
      (node (ref "4051") (pin "9") (pinfunction "C_9") (pintype "input"))
      (node (ref "MELODY") (pin "3") (pinfunction "3_3") (pintype "passive"))
      (node (ref "R25") (pin "2") (pinfunction "2_2") (pintype "passive"))
    )
    (net (code "19") (name "MOXO") (class "Default")
      (node (ref "4051") (pin "10") (pinfunction "B_10") (pintype "input"))
      (node (ref "MELODY") (pin "2") (pinfunction "2_2") (pintype "passive"))
      (node (ref "R24") (pin "2") (pinfunction "2_2") (pintype "passive"))
    )
    (net (code "20") (name "MXOO") (class "Default")
      (node (ref "4051") (pin "11") (pinfunction "A_11") (pintype "input"))
      (node (ref "MELODY") (pin "1") (pinfunction "1_1") (pintype "passive"))
      (node (ref "R23") (pin "2") (pinfunction "2_2") (pintype "passive"))
    )
    (net (code "21") (name "Net-(4017A-Q2)") (class "Default")
      (node (ref "4017") (pin "4") (pinfunction "Q2_4") (pintype "output"))
      (node (ref "4051") (pin "13") (pinfunction "X0_13") (pintype "bidirectional"))
    )
    (net (code "22") (name "Net-(4017A-Q3)") (class "Default")
      (node (ref "4017") (pin "7") (pinfunction "Q3_7") (pintype "output"))
      (node (ref "4051") (pin "14") (pinfunction "X1_14") (pintype "bidirectional"))
    )
    (net (code "23") (name "Net-(4017A-Q4)") (class "Default")
      (node (ref "4017") (pin "10") (pinfunction "Q4_10") (pintype "output"))
      (node (ref "4051") (pin "15") (pinfunction "X2_15") (pintype "bidirectional"))
    )
    (net (code "24") (name "Net-(4017A-Q5)") (class "Default")
      (node (ref "4017") (pin "1") (pinfunction "Q5_1") (pintype "output"))
      (node (ref "4051") (pin "12") (pinfunction "X3_12") (pintype "bidirectional"))
    )
    (net (code "25") (name "Net-(4017A-Q6)") (class "Default")
      (node (ref "4017") (pin "5") (pinfunction "Q6_5") (pintype "output"))
      (node (ref "4051") (pin "1") (pinfunction "X4_1") (pintype "bidirectional"))
    )
    (net (code "26") (name "Net-(4017A-Q7)") (class "Default")
      (node (ref "4017") (pin "6") (pinfunction "Q7_6") (pintype "output"))
      (node (ref "4051") (pin "5") (pinfunction "X5_5") (pintype "bidirectional"))
    )
    (net (code "27") (name "Net-(4017A-Q8)") (class "Default")
      (node (ref "4017") (pin "9") (pinfunction "Q8_9") (pintype "output"))
      (node (ref "4051") (pin "2") (pinfunction "X6_2") (pintype "bidirectional"))
    )
    (net (code "28") (name "Net-(4017A-Q9)") (class "Default")
      (node (ref "4017") (pin "11") (pinfunction "Q9_11") (pintype "output"))
      (node (ref "4051") (pin "4") (pinfunction "X7_4") (pintype "bidirectional"))
    )
    (net (code "29") (name "Net-(4017A-RES)") (class "Default")
      (node (ref "4017") (pin "15") (pinfunction "RES_15") (pintype "input"))
      (node (ref "4051") (pin "3") (pinfunction "X_3") (pintype "bidirectional"))
    )
    (net (code "30") (name "Net-(4046A-CX-Pad6)") (class "Default")
      (node (ref "4046") (pin "6") (pinfunction "CX_6") (pintype "input"))
      (node (ref "C6") (pin "1") (pinfunction "1_1") (pintype "passive"))
    )
    (net (code "31") (name "Net-(4046A-CX-Pad7)") (class "Default")
      (node (ref "4046") (pin "7") (pinfunction "CX_7") (pintype "input"))
      (node (ref "C6") (pin "2") (pinfunction "2_2") (pintype "passive"))
    )
    (net (code "32") (name "Net-(4046A-R1)") (class "Default")
      (node (ref "4046") (pin "11") (pinfunction "R1_11") (pintype "input"))
      (node (ref "R15") (pin "2") (pinfunction "2_2") (pintype "passive"))
    )
    (net (code "33") (name "Net-(4094A-D)") (class "Default")
      (node (ref "4094") (pin "2") (pinfunction "D_2") (pintype "input"))
      (node (ref "ERASE") (pin "3") (pinfunction "2_3") (pintype "passive"))
      (node (ref "R26") (pin "1") (pinfunction "1_1") (pintype "passive"))
      (node (ref "WRITE") (pin "3") (pinfunction "2_3") (pintype "passive"))
    )
    (net (code "34") (name "Net-(40106A-I)") (class "Default")
      (node (ref "40106") (pin "1") (pinfunction "I_1") (pintype "input"))
      (node (ref "C19") (pin "1") (pinfunction "1_1") (pintype "passive"))
      (node (ref "FREQ") (pin "2") (pinfunction "S_2") (pintype "passive"))
      (node (ref "R28") (pin "2") (pinfunction "2_2") (pintype "passive"))
    )
    (net (code "35") (name "Net-(40106A-O)") (class "Default")
      (node (ref "40106") (pin "2") (pinfunction "O_2") (pintype "output"))
      (node (ref "40106") (pin "3") (pinfunction "I_3") (pintype "input"))
      (node (ref "FREQ") (pin "3") (pinfunction "E_3") (pintype "passive"))
      (node (ref "R28") (pin "1") (pinfunction "1_1") (pintype "passive"))
    )
    (net (code "36") (name "Net-(40106B-O)") (class "Default")
      (node (ref "40106") (pin "4") (pinfunction "O_4") (pintype "output"))
      (node (ref "40106") (pin "5") (pinfunction "I_5") (pintype "input"))
    )
    (net (code "37") (name "Net-(B1-PadVIN)") (class "Default")
      (node (ref "B1") (pin "VIN") (pinfunction "VIN_VIN") (pintype "power_in"))
      (node (ref "TNSYPWR") (pin "2") (pinfunction "2_2") (pintype "passive"))
    )
    (net (code "38") (name "Net-(C20-+)") (class "Default")
      (node (ref "C20") (pin "1") (pinfunction "+_1") (pintype "passive"))
      (node (ref "PT2399") (pin "2") (pinfunction "2_2") (pintype "bidirectional"))
    )
    (net (code "39") (name "Net-(C21-Pad1)") (class "Default")
      (node (ref "C21") (pin "1") (pinfunction "1_1") (pintype "passive"))
      (node (ref "PT2399") (pin "8") (pinfunction "8_8") (pintype "bidirectional"))
    )
    (net (code "40") (name "Net-(C22-Pad2)") (class "Default")
      (node (ref "C22") (pin "2") (pinfunction "2_2") (pintype "passive"))
      (node (ref "PT2399") (pin "7") (pinfunction "7_7") (pintype "bidirectional"))
    )
    (net (code "41") (name "Net-(C24-Pad2)") (class "Default")
      (node (ref "C24") (pin "2") (pinfunction "2_2") (pintype "passive"))
      (node (ref "PT2399") (pin "11") (pinfunction "11_11") (pintype "bidirectional"))
    )
    (net (code "42") (name "Net-(C25-Pad1)") (class "Default")
      (node (ref "C25") (pin "1") (pinfunction "1_1") (pintype "passive"))
      (node (ref "PT2399") (pin "10") (pinfunction "10_10") (pintype "bidirectional"))
    )
    (net (code "43") (name "Net-(C25-Pad2)") (class "Default")
      (node (ref "C25") (pin "2") (pinfunction "2_2") (pintype "passive"))
      (node (ref "PT2399") (pin "9") (pinfunction "9_9") (pintype "bidirectional"))
    )
    (net (code "44") (name "Net-(C26--)") (class "Default")
      (node (ref "C26") (pin "2") (pinfunction "-_2") (pintype "passive"))
      (node (ref "VR4") (pin "1") (pinfunction "1_1") (pintype "passive"))
    )
    (net (code "45") (name "Net-(CLOCK-C)") (class "Default")
      (node (ref "CLOCK") (pin "K") (pinfunction "C_K") (pintype "passive"))
      (node (ref "R18") (pin "2") (pinfunction "2_2") (pintype "passive"))
    )
    (net (code "46") (name "Net-(CLOCKOUT-2)") (class "Default")
      (node (ref "CLOCKOUT") (pin "P$1_TIP") (pinfunction "2_P$1_TIP") (pintype "passive"))
      (node (ref "D1") (pin "C") (pinfunction "C_C") (pintype "passive"))
      (node (ref "D2") (pin "C") (pinfunction "C_C") (pintype "passive"))
    )
    (net (code "47") (name "Net-(D3-PadA)") (class "Default")
      (node (ref "D3") (pin "A") (pinfunction "A_A") (pintype "passive"))
      (node (ref "J1") (pin "PWR") (pinfunction "PWR_PWR") (pintype "bidirectional"))
    )
    (net (code "48") (name "Net-(FDBK-A)") (class "Default")
      (node (ref "C24") (pin "1") (pinfunction "1_1") (pintype "passive"))
      (node (ref "FDBK") (pin "1") (pinfunction "A_1") (pintype "passive"))
      (node (ref "MIX") (pin "1") (pinfunction "A_1") (pintype "passive"))
      (node (ref "PT2399") (pin "12") (pinfunction "12_12") (pintype "bidirectional"))
    )
    (net (code "49") (name "Net-(FDBK-S)") (class "Default")
      (node (ref "FDBK") (pin "2") (pinfunction "S_2") (pintype "passive"))
      (node (ref "PT2399") (pin "15") (pinfunction "15_15") (pintype "bidirectional"))
      (node (ref "R32") (pin "2") (pinfunction "2_2") (pintype "passive"))
    )
    (net (code "50") (name "Net-(LM358-2A-+IN)") (class "Default")
      (node (ref "LM358-2") (pin "3") (pinfunction "+IN_3") (pintype "input"))
      (node (ref "R27") (pin "2") (pinfunction "2_2") (pintype "passive"))
      (node (ref "R29") (pin "1") (pinfunction "1_1") (pintype "passive"))
    )
    (net (code "51") (name "Net-(LM358-2A--IN)") (class "Default")
      (node (ref "D1") (pin "A") (pinfunction "A_A") (pintype "passive"))
      (node (ref "LM358-2") (pin "1") (pinfunction "OUT_1") (pintype "output"))
      (node (ref "LM358-2") (pin "2") (pinfunction "-IN_2") (pintype "input"))
    )
    (net (code "52") (name "Net-(MCP41050-PB0)") (class "Default")
      (node (ref "MCP41050") (pin "7") (pinfunction "PB0_7") (pintype "passive"))
      (node (ref "R30") (pin "1") (pinfunction "1_1") (pintype "passive"))
    )
    (net (code "53") (name "Net-(MIX-E)") (class "Default")
      (node (ref "MIX") (pin "3") (pinfunction "E_3") (pintype "passive"))
      (node (ref "R33") (pin "2") (pinfunction "2_2") (pintype "passive"))
    )
    (net (code "54") (name "Net-(MS4-C)") (class "Default")
      (node (ref "MS4") (pin "K") (pinfunction "C_K") (pintype "passive"))
      (node (ref "R21") (pin "2") (pinfunction "2_2") (pintype "passive"))
    )
    (net (code "55") (name "Net-(OUTPUT-2)") (class "Default")
      (node (ref "OUTPUT") (pin "P$1_TIP") (pinfunction "2_P$1_TIP") (pintype "passive"))
      (node (ref "VR4") (pin "2") (pinfunction "2_2") (pintype "passive"))
    )
    (net (code "56") (name "Net-(PT2399-Pad6)") (class "Default")
      (node (ref "PT2399") (pin "6") (pinfunction "6_6") (pintype "bidirectional"))
      (node (ref "R30") (pin "2") (pinfunction "2_2") (pintype "passive"))
    )
    (net (code "57") (name "Net-(PT2399-Pad16)") (class "Default")
      (node (ref "PT2399") (pin "16") (pinfunction "16_16") (pintype "bidirectional"))
      (node (ref "R31") (pin "2") (pinfunction "2_2") (pintype "passive"))
      (node (ref "R32") (pin "1") (pinfunction "1_1") (pintype "passive"))
    )
    (net (code "58") (name "Net-(R16-Pad2)") (class "Default")
      (node (ref "R16") (pin "2") (pinfunction "2_2") (pintype "passive"))
      (node (ref "R17") (pin "2") (pinfunction "2_2") (pintype "passive"))
      (node (ref "T1") (pin "B") (pinfunction "B_B") (pintype "passive"))
    )
    (net (code "59") (name "Net-(R18-Pad1)") (class "Default")
      (node (ref "R18") (pin "1") (pinfunction "1_1") (pintype "passive"))
      (node (ref "T1") (pin "C") (pinfunction "C_C") (pintype "passive"))
    )
    (net (code "60") (name "Net-(R19-Pad2)") (class "Default")
      (node (ref "R19") (pin "2") (pinfunction "2_2") (pintype "passive"))
      (node (ref "R20") (pin "2") (pinfunction "2_2") (pintype "passive"))
      (node (ref "T2") (pin "B") (pinfunction "B_B") (pintype "passive"))
    )
    (net (code "61") (name "Net-(R21-Pad1)") (class "Default")
      (node (ref "R21") (pin "1") (pinfunction "1_1") (pintype "passive"))
      (node (ref "T2") (pin "C") (pinfunction "C_C") (pintype "passive"))
    )
    (net (code "62") (name "Net-(R22-Pad2)") (class "Default")
      (node (ref "R22") (pin "2") (pinfunction "2_2") (pintype "passive"))
      (node (ref "WRITE") (pin "1") (pinfunction "1_1") (pintype "passive"))
    )
    (net (code "63") (name "OOX") (class "Default")
      (node (ref "339") (pin "11") (pinfunction "+IN_11") (pintype "input"))
      (node (ref "PATTERN") (pin "3") (pinfunction "3_3") (pintype "passive"))
      (node (ref "R8") (pin "2") (pinfunction "2_2") (pintype "passive"))
    )
    (net (code "64") (name "OUT") (class "Default")
      (node (ref "C26") (pin "1") (pinfunction "+_1") (pintype "passive"))
      (node (ref "MIX") (pin "2") (pinfunction "S_2") (pintype "passive"))
    )
    (net (code "65") (name "OXO") (class "Default")
      (node (ref "339") (pin "9") (pinfunction "+IN_9") (pintype "input"))
      (node (ref "PATTERN") (pin "2") (pinfunction "2_2") (pintype "passive"))
      (node (ref "R3") (pin "2") (pinfunction "2_2") (pintype "passive"))
    )
    (net (code "66") (name "PLLCLOCKOUT") (class "Default")
      (node (ref "4040") (pin "10") (pinfunction "P1_10") (pintype "input"))
      (node (ref "4046") (pin "4") (pinfunction "VCOOUT_4") (pintype "output"))
      (node (ref "CLOCKDIV") (pin "1") (pinfunction "1_1") (pintype "passive"))
      (node (ref "CLOCKDIV") (pin "2") (pinfunction "2_2") (pintype "passive"))
      (node (ref "JP4") (pin "1") (pinfunction "1_1") (pintype "passive"))
    )
    (net (code "67") (name "PLL{slash}2") (class "Default")
      (node (ref "4040") (pin "9") (pinfunction "Q1_9") (pintype "output"))
      (node (ref "CLOCKDIV") (pin "3") (pinfunction "3_3") (pintype "passive"))
      (node (ref "CLOCKDIV") (pin "4") (pinfunction "4_4") (pintype "passive"))
      (node (ref "JP4") (pin "3") (pinfunction "3_3") (pintype "passive"))
    )
    (net (code "68") (name "PLL{slash}4") (class "Default")
      (node (ref "4040") (pin "7") (pinfunction "Q2_7") (pintype "output"))
      (node (ref "CLOCKDIV") (pin "5") (pinfunction "5_5") (pintype "passive"))
      (node (ref "CLOCKDIV") (pin "6") (pinfunction "6_6") (pintype "passive"))
      (node (ref "JP4") (pin "5") (pinfunction "5_5") (pintype "passive"))
    )
    (net (code "69") (name "PLL{slash}8") (class "Default")
      (node (ref "4040") (pin "6") (pinfunction "Q3_6") (pintype "output"))
      (node (ref "CLOCKDIV") (pin "7") (pinfunction "7_7") (pintype "passive"))
      (node (ref "CLOCKDIV") (pin "8") (pinfunction "8_8") (pintype "passive"))
      (node (ref "JP4") (pin "7") (pinfunction "7_7") (pintype "passive"))
    )
    (net (code "70") (name "PLL{slash}16") (class "Default")
      (node (ref "4040") (pin "5") (pinfunction "Q4_5") (pintype "output"))
      (node (ref "CLOCKDIV") (pin "10") (pinfunction "10_10") (pintype "passive"))
      (node (ref "CLOCKDIV") (pin "9") (pinfunction "9_9") (pintype "passive"))
    )
    (net (code "71") (name "PLL{slash}32") (class "Default")
      (node (ref "4040") (pin "3") (pinfunction "Q5_3") (pintype "output"))
      (node (ref "CLOCKDIV") (pin "11") (pinfunction "11_11") (pintype "passive"))
      (node (ref "CLOCKDIV") (pin "12") (pinfunction "12_12") (pintype "passive"))
    )
    (net (code "72") (name "RESET") (class "Default")
      (node (ref "339") (pin "5") (pinfunction "+IN_5") (pintype "input"))
      (node (ref "PATTERN") (pin "4") (pinfunction "4_4") (pintype "passive"))
      (node (ref "R1") (pin "2") (pinfunction "2_2") (pintype "passive"))
    )
    (net (code "73") (name "SCL") (class "Default")
      (node (ref "B1") (pin "19") (pinfunction "A5/19/SCL0_19") (pintype "bidirectional"))
      (node (ref "OL96$1") (pin "SCL") (pinfunction "SCL_SCL") (pintype "bidirectional"))
      (node (ref "OL96$2") (pin "SCL") (pinfunction "SCL_SCL") (pintype "bidirectional"))
      (node (ref "R5") (pin "1") (pinfunction "1_1") (pintype "passive"))
    )
    (net (code "74") (name "SDA") (class "Default")
      (node (ref "B1") (pin "18") (pinfunction "A4/18/SDA0_18") (pintype "bidirectional"))
      (node (ref "OL96$1") (pin "SDA") (pinfunction "SDA_SDA") (pintype "bidirectional"))
      (node (ref "OL96$2") (pin "SDA") (pinfunction "SDA_SDA") (pintype "bidirectional"))
      (node (ref "R9") (pin "1") (pinfunction "1_1") (pintype "passive"))
    )
    (net (code "75") (name "SPEEDPIN") (class "Default")
      (node (ref "B1") (pin "15") (pinfunction "A1/15_15") (pintype "bidirectional"))
      (node (ref "LM358-1") (pin "3") (pinfunction "+IN_3") (pintype "input"))
      (node (ref "SPEED") (pin "2") (pinfunction "S_2") (pintype "passive"))
    )
    (net (code "76") (name "SPEEDYBUFF") (class "Default")
      (node (ref "4046") (pin "9") (pinfunction "VCOIN_9") (pintype "input"))
      (node (ref "LM358-1") (pin "1") (pinfunction "OUT_1") (pintype "output"))
      (node (ref "LM358-1") (pin "2") (pinfunction "-IN_2") (pintype "input"))
    )
    (net (code "77") (name "SR1") (class "Default")
      (node (ref "4094") (pin "4") (pinfunction "Q1_4") (pintype "output"))
      (node (ref "SHIFTREG") (pin "1") (pinfunction "1_1") (pintype "passive"))
      (node (ref "SHIFTREG") (pin "2") (pinfunction "2_2") (pintype "passive"))
    )
    (net (code "78") (name "SR2") (class "Default")
      (node (ref "4094") (pin "5") (pinfunction "Q2_5") (pintype "output"))
      (node (ref "SHIFTREG") (pin "3") (pinfunction "3_3") (pintype "passive"))
      (node (ref "SHIFTREG") (pin "4") (pinfunction "4_4") (pintype "passive"))
    )
    (net (code "79") (name "SR3") (class "Default")
      (node (ref "4094") (pin "6") (pinfunction "Q3_6") (pintype "output"))
      (node (ref "SHIFTREG") (pin "5") (pinfunction "5_5") (pintype "passive"))
      (node (ref "SHIFTREG") (pin "6") (pinfunction "6_6") (pintype "passive"))
    )
    (net (code "80") (name "SR4") (class "Default")
      (node (ref "4094") (pin "7") (pinfunction "Q4_7") (pintype "output"))
      (node (ref "SHIFTREG") (pin "7") (pinfunction "7_7") (pintype "passive"))
      (node (ref "SHIFTREG") (pin "8") (pinfunction "8_8") (pintype "passive"))
    )
    (net (code "81") (name "SR5") (class "Default")
      (node (ref "4094") (pin "14") (pinfunction "Q5_14") (pintype "output"))
      (node (ref "SHIFTREG") (pin "10") (pinfunction "10_10") (pintype "passive"))
      (node (ref "SHIFTREG") (pin "9") (pinfunction "9_9") (pintype "passive"))
    )
    (net (code "82") (name "SR6") (class "Default")
      (node (ref "4094") (pin "13") (pinfunction "Q6_13") (pintype "output"))
      (node (ref "SHIFTREG") (pin "11") (pinfunction "11_11") (pintype "passive"))
      (node (ref "SHIFTREG") (pin "12") (pinfunction "12_12") (pintype "passive"))
    )
    (net (code "83") (name "SR7") (class "Default")
      (node (ref "4094") (pin "12") (pinfunction "Q7_12") (pintype "output"))
      (node (ref "SHIFTREG") (pin "13") (pinfunction "13_13") (pintype "passive"))
      (node (ref "SHIFTREG") (pin "14") (pinfunction "14_14") (pintype "passive"))
    )
    (net (code "84") (name "SR8") (class "Default")
      (node (ref "4094") (pin "11") (pinfunction "Q8_11") (pintype "output"))
      (node (ref "R26") (pin "2") (pinfunction "2_2") (pintype "passive"))
      (node (ref "SHIFTREG") (pin "15") (pinfunction "15_15") (pintype "passive"))
      (node (ref "SHIFTREG") (pin "16") (pinfunction "16_16") (pintype "passive"))
    )
    (net (code "85") (name "TNSYOOX") (class "Default")
      (node (ref "339") (pin "13") (pinfunction "OUT_13") (pintype "output"))
      (node (ref "B1") (pin "6") (pinfunction "6*_6") (pintype "bidirectional"))
      (node (ref "R13") (pin "1") (pinfunction "1_1") (pintype "passive"))
    )
    (net (code "86") (name "TNSYOXO") (class "Default")
      (node (ref "339") (pin "14") (pinfunction "OUT_14") (pintype "output"))
      (node (ref "B1") (pin "5") (pinfunction "5*_5") (pintype "bidirectional"))
      (node (ref "R11") (pin "1") (pinfunction "1_1") (pintype "passive"))
    )
    (net (code "87") (name "TNSYRES") (class "Default")
      (node (ref "339") (pin "2") (pinfunction "OUT_2") (pintype "output"))
      (node (ref "B1") (pin "3") (pinfunction "3*_3") (pintype "bidirectional"))
      (node (ref "R4") (pin "1") (pinfunction "1_1") (pintype "passive"))
    )
    (net (code "88") (name "TNSYXOO") (class "Default")
      (node (ref "339") (pin "1") (pinfunction "OUT_1") (pintype "output"))
      (node (ref "B1") (pin "4") (pinfunction "4*_4") (pintype "bidirectional"))
      (node (ref "R7") (pin "1") (pinfunction "1_1") (pintype "passive"))
    )
    (net (code "89") (name "VBAT") (class "Default")
      (node (ref "B1") (pin "VBAT") (pinfunction "VBAT_VBAT") (pintype "power_in"))
    )
    (net (code "90") (name "VUSB") (class "Default")
      (node (ref "B1") (pin "VUSB") (pinfunction "VUSB_VUSB") (pintype "power_in"))
    )
    (net (code "91") (name "XOO") (class "Default")
      (node (ref "339") (pin "7") (pinfunction "+IN_7") (pintype "input"))
      (node (ref "PATTERN") (pin "1") (pinfunction "1_1") (pintype "passive"))
      (node (ref "R2") (pin "2") (pinfunction "2_2") (pintype "passive"))
    )
    (net (code "92") (name "unconnected-(4017A-CO-Pad12)") (class "Default")
      (node (ref "4017") (pin "12") (pinfunction "CO_12") (pintype "output"))
    )
    (net (code "93") (name "unconnected-(4017A-Q1-Pad2)") (class "Default")
      (node (ref "4017") (pin "2") (pinfunction "Q1_2") (pintype "output"))
    )
    (net (code "94") (name "unconnected-(4040A-Q6-Pad2)") (class "Default")
      (node (ref "4040") (pin "2") (pinfunction "Q6_2") (pintype "output"))
    )
    (net (code "95") (name "unconnected-(4040A-Q7-Pad4)") (class "Default")
      (node (ref "4040") (pin "4") (pinfunction "Q7_4") (pintype "output"))
    )
    (net (code "96") (name "unconnected-(4040A-Q8-Pad13)") (class "Default")
      (node (ref "4040") (pin "13") (pinfunction "Q8_13") (pintype "output"))
    )
    (net (code "97") (name "unconnected-(4040A-Q9-Pad12)") (class "Default")
      (node (ref "4040") (pin "12") (pinfunction "Q9_12") (pintype "output"))
    )
    (net (code "98") (name "unconnected-(4040A-Q10-Pad14)") (class "Default")
      (node (ref "4040") (pin "14") (pinfunction "Q10_14") (pintype "output"))
    )
    (net (code "99") (name "unconnected-(4040A-Q11-Pad15)") (class "Default")
      (node (ref "4040") (pin "15") (pinfunction "Q11_15") (pintype "output"))
    )
    (net (code "100") (name "unconnected-(4040A-Q12-Pad1)") (class "Default")
      (node (ref "4040") (pin "1") (pinfunction "Q12_1") (pintype "output"))
    )
    (net (code "101") (name "unconnected-(4046A-CIN-Pad3)") (class "Default")
      (node (ref "4046") (pin "3") (pinfunction "CIN_3") (pintype "input"))
    )
    (net (code "102") (name "unconnected-(4046A-DEMO-Pad10)") (class "Default")
      (node (ref "4046") (pin "10") (pinfunction "DEMO_10") (pintype "output"))
    )
    (net (code "103") (name "unconnected-(4046A-PC1-Pad2)") (class "Default")
      (node (ref "4046") (pin "2") (pinfunction "PC1_2") (pintype "output"))
    )
    (net (code "104") (name "unconnected-(4046A-PC2-Pad13)") (class "Default")
      (node (ref "4046") (pin "13") (pinfunction "PC2_13") (pintype "output"))
    )
    (net (code "105") (name "unconnected-(4046A-PP-Pad1)") (class "Default")
      (node (ref "4046") (pin "1") (pinfunction "PP_1") (pintype "output"))
    )
    (net (code "106") (name "unconnected-(4046A-R2-Pad12)") (class "Default")
      (node (ref "4046") (pin "12") (pinfunction "R2_12") (pintype "input"))
    )
    (net (code "107") (name "unconnected-(4046A-SIGIN-Pad14)") (class "Default")
      (node (ref "4046") (pin "14") (pinfunction "SIGIN_14") (pintype "input"))
    )
    (net (code "108") (name "unconnected-(4046A-ZEN-Pad15)") (class "Default")
      (node (ref "4046") (pin "15") (pinfunction "ZEN_15") (pintype "input"))
    )
    (net (code "109") (name "unconnected-(4094A-QS*-Pad10)") (class "Default")
      (node (ref "4094") (pin "10") (pinfunction "QS*_10") (pintype "output"))
    )
    (net (code "110") (name "unconnected-(4094A-QS-Pad9)") (class "Default")
      (node (ref "4094") (pin "9") (pinfunction "QS_9") (pintype "output"))
    )
    (net (code "111") (name "unconnected-(40106D-O-Pad8)") (class "Default")
      (node (ref "40106") (pin "8") (pinfunction "O_8") (pintype "output"))
    )
    (net (code "112") (name "unconnected-(40106E-O-Pad10)") (class "Default")
      (node (ref "40106") (pin "10") (pinfunction "O_10") (pintype "output"))
    )
    (net (code "113") (name "unconnected-(40106F-O-Pad12)") (class "Default")
      (node (ref "40106") (pin "12") (pinfunction "O_12") (pintype "output"))
    )
    (net (code "114") (name "unconnected-(B1-0{slash}RX1-Pad0)") (class "Default")
      (node (ref "B1") (pin "0") (pinfunction "0/RX1_0") (pintype "bidirectional"))
    )
    (net (code "115") (name "unconnected-(B1-1{slash}TX1-Pad1)") (class "Default")
      (node (ref "B1") (pin "1") (pinfunction "1/TX1_1") (pintype "bidirectional"))
    )
    (net (code "116") (name "unconnected-(B1-7{slash}RX3-Pad7)") (class "Default")
      (node (ref "B1") (pin "7") (pinfunction "7/RX3_7") (pintype "bidirectional"))
    )
    (net (code "117") (name "unconnected-(B1-8{slash}TX3-Pad8)") (class "Default")
      (node (ref "B1") (pin "8") (pinfunction "8/TX3_8") (pintype "bidirectional"))
    )
    (net (code "118") (name "unconnected-(B1-12{slash}DIN-Pad12)") (class "Default")
      (node (ref "B1") (pin "12") (pinfunction "12/DIN_12") (pintype "bidirectional"))
    )
    (net (code "119") (name "unconnected-(B1-A2{slash}16-Pad16)") (class "Default")
      (node (ref "B1") (pin "16") (pinfunction "A2/16_16") (pintype "bidirectional"))
    )
    (net (code "120") (name "unconnected-(B1-A3{slash}17-Pad17)") (class "Default")
      (node (ref "B1") (pin "17") (pinfunction "A3/17_17") (pintype "bidirectional"))
    )
    (net (code "121") (name "unconnected-(B1-A6{slash}20*-Pad20)") (class "Default")
      (node (ref "B1") (pin "20") (pinfunction "A6/20*_20") (pintype "bidirectional"))
    )
    (net (code "122") (name "unconnected-(B1-A7{slash}21*-Pad21)") (class "Default")
      (node (ref "B1") (pin "21") (pinfunction "A7/21*_21") (pintype "bidirectional"))
    )
    (net (code "123") (name "unconnected-(B1-A8{slash}22*-Pad22)") (class "Default")
      (node (ref "B1") (pin "22") (pinfunction "A8/22*_22") (pintype "bidirectional"))
    )
    (net (code "124") (name "unconnected-(B1-A9{slash}23*-Pad23)") (class "Default")
      (node (ref "B1") (pin "23") (pinfunction "A9/23*_23") (pintype "bidirectional"))
    )
    (net (code "125") (name "unconnected-(B1-Pad2)") (class "Default")
      (node (ref "B1") (pin "2") (pinfunction "2_2") (pintype "bidirectional"))
    )
    (net (code "126") (name "unconnected-(B1-PadA10)") (class "Default")
      (node (ref "B1") (pin "A10") (pinfunction "A10_A10") (pintype "bidirectional"))
    )
    (net (code "127") (name "unconnected-(B1-PadA11)") (class "Default")
      (node (ref "B1") (pin "A11") (pinfunction "A11_A11") (pintype "bidirectional"))
    )
    (net (code "128") (name "unconnected-(B1-PadA14{slash}DAC)") (class "Default")
      (node (ref "B1") (pin "A14/DAC") (pinfunction "A14/DAC_A14/DAC") (pintype "bidirectional"))
    )
    (net (code "129") (name "unconnected-(B1-PadAREF)") (class "Default")
      (node (ref "B1") (pin "AREF") (pinfunction "AREF_AREF") (pintype "bidirectional"))
    )
    (net (code "130") (name "unconnected-(B1-PadPROG)") (class "Default")
      (node (ref "B1") (pin "PROG") (pinfunction "PROG_PROG") (pintype "bidirectional"))
    )
    (net (code "131") (name "unconnected-(CLOCKOUT-3-PadP$2_SWITCH)") (class "Default")
      (node (ref "CLOCKOUT") (pin "P$2_SWITCH") (pinfunction "3_P$2_SWITCH") (pintype "passive"))
    )
    (net (code "132") (name "unconnected-(FDBK-E-Pad3)") (class "Default")
      (node (ref "FDBK") (pin "3") (pinfunction "E_3") (pintype "passive"))
    )
    (net (code "133") (name "unconnected-(FREQ-A-Pad1)") (class "Default")
      (node (ref "FREQ") (pin "1") (pinfunction "A_1") (pintype "passive"))
    )
    (net (code "134") (name "unconnected-(OUTPUT-3-PadP$2_SWITCH)") (class "Default")
      (node (ref "OUTPUT") (pin "P$2_SWITCH") (pinfunction "3_P$2_SWITCH") (pintype "passive"))
    )
    (net (code "135") (name "unconnected-(PT2399-Pad5)") (class "Default")
      (node (ref "PT2399") (pin "5") (pinfunction "5_5") (pintype "bidirectional"))
    )
    (net (code "136") (name "unconnected-(PT2399-Pad13)") (class "Default")
      (node (ref "PT2399") (pin "13") (pinfunction "13_13") (pintype "bidirectional"))
    )
    (net (code "137") (name "unconnected-(PT2399-Pad14)") (class "Default")
      (node (ref "PT2399") (pin "14") (pinfunction "14_14") (pintype "bidirectional"))
    )
  )
)
